# mimic1575.net
KiCad netlist of a schematic drawn in EAGLE
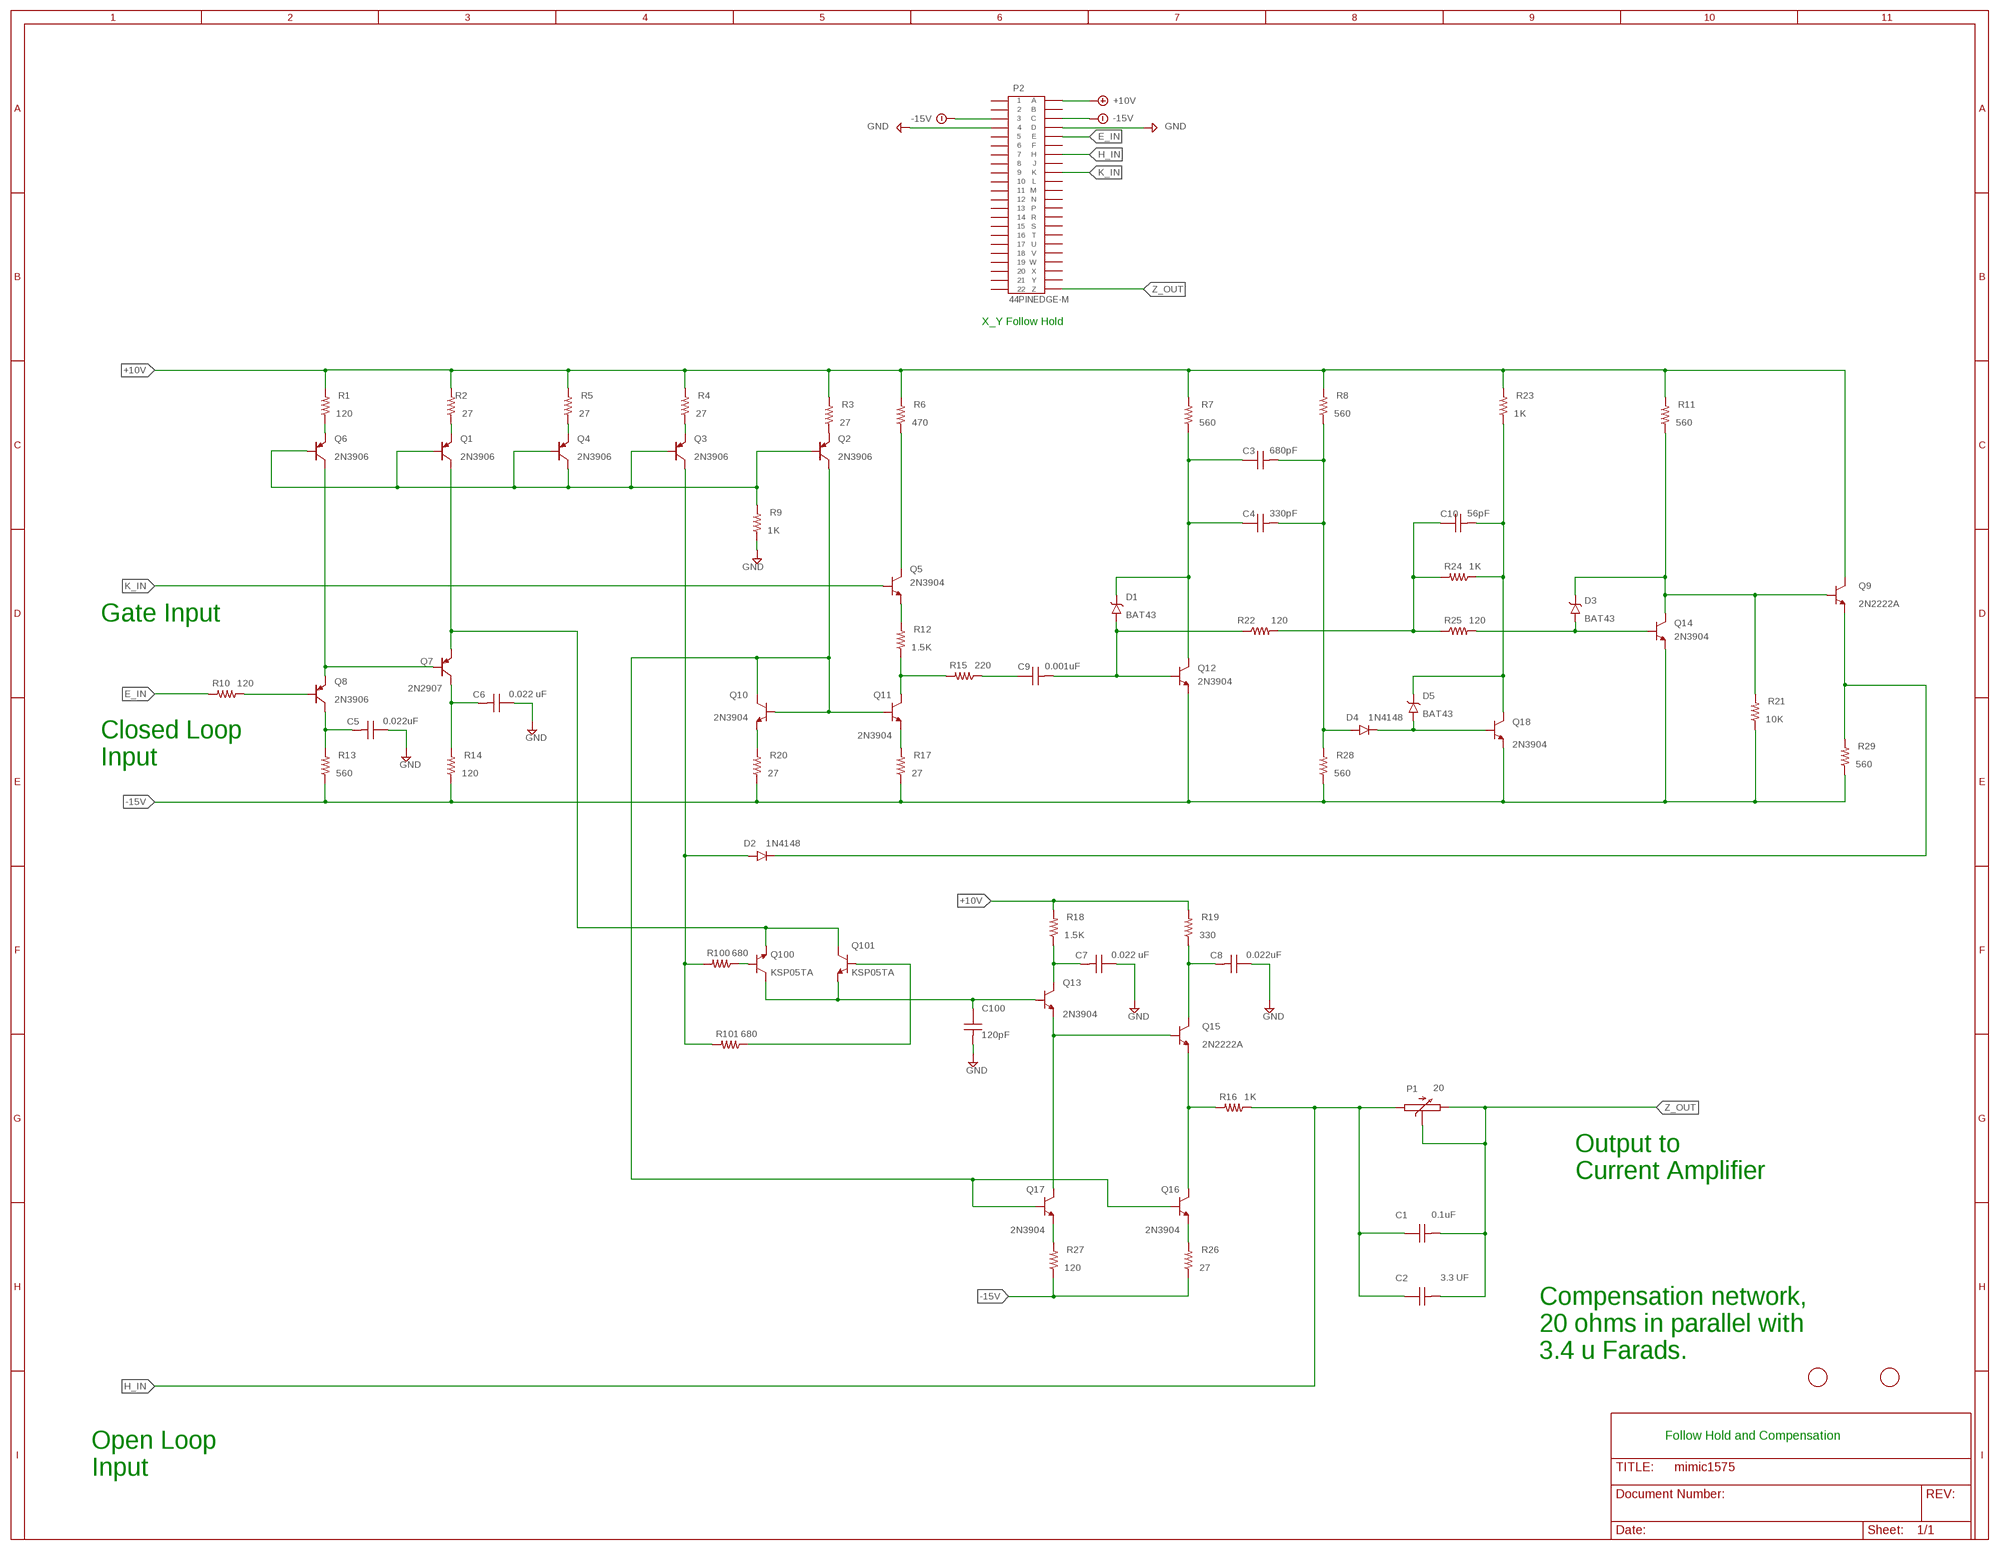
[diagram p0: schematic, sheet 1]

(export (version "E")
  (design (tool "Eeschema 10.0.6"))
  (components
    (comp (ref "C1")
      (value "0.1uF")
      (footprint "eagle-import:5MM_TH")
      (fields (field (name "MPN") "FA26X8R2A104KNU06"))
      (libsource (lib "eagle-import") (part "CAP0.1UF100V"))
    )
    (comp (ref "C2")
      (value "3.3 UF")
      (footprint "eagle-import:ECW-FD2W335K")
      (libsource (lib "eagle-import") (part "ECW-FD2W335K"))
    )
    (comp (ref "C3")
      (value "680pF")
      (footprint "eagle-import:5MM_TH")
      (fields (field (name "MPN") "FA26X8R2A104KNU06") (field (name "MPN_1") "1000 pf"))
      (libsource (lib "eagle-import") (part "CAP0.1UF100V"))
    )
    (comp (ref "C4")
      (value "330pF")
      (footprint "eagle-import:5MM_TH")
      (fields (field (name "MPN") "FA26X8R2A104KNU06") (field (name "MPN_1") "1000 pf"))
      (libsource (lib "eagle-import") (part "CAP0.1UF100V"))
    )
    (comp (ref "C5")
      (value "0.022uF")
      (footprint "eagle-import:CAP-ZERO-PT-ZERO-22UF-250V-FILM")
      (libsource (lib "eagle-import") (part "ECQ-E2223JF"))
    )
    (comp (ref "C6")
      (value "0.022 uF")
      (footprint "eagle-import:CAP-ZERO-PT-ZERO-22UF-250V-FILM")
      (libsource (lib "eagle-import") (part "ECQ-E2223JF"))
    )
    (comp (ref "C7")
      (value "0.022 uF")
      (footprint "eagle-import:CAP-ZERO-PT-ZERO-22UF-250V-FILM")
      (libsource (lib "eagle-import") (part "ECQ-E2223JF"))
    )
    (comp (ref "C8")
      (value "0.022uF")
      (footprint "eagle-import:CAP-ZERO-PT-ZERO-22UF-250V-FILM")
      (libsource (lib "eagle-import") (part "ECQ-E2223JF"))
    )
    (comp (ref "C9")
      (value "0.001uF")
      (footprint "eagle-import:5MM_TH")
      (fields (field (name "MPN") "FA26X8R2A104KNU06") (field (name "MPN_1") "1000 pf"))
      (libsource (lib "eagle-import") (part "CAP0.1UF100V"))
    )
    (comp (ref "C10")
      (value "56pF")
      (footprint "eagle-import:5MM_TH")
      (fields (field (name "MPN") "FA26X8R2A104KNU06") (field (name "MPN_1") "68 pF"))
      (libsource (lib "eagle-import") (part "CAP0.1UF100V"))
    )
    (comp (ref "C100")
      (value "120pF")
      (footprint "eagle-import:5MM_TH")
      (fields (field (name "MPN") "FA26X8R2A104KNU06") (field (name "MPN_1") "1000 pf"))
      (libsource (lib "eagle-import") (part "CAP0.1UF100V"))
    )
    (comp (ref "D1")
      (value "BAT43")
      (footprint "eagle-import:DO35-7")
      (libsource (lib "eagle-import") (part "1N754A"))
    )
    (comp (ref "D2")
      (value "1N4148")
      (footprint "eagle-import:DO35-7")
      (libsource (lib "eagle-import") (part "1N4148"))
    )
    (comp (ref "D3")
      (value "BAT43")
      (footprint "eagle-import:DO35-7")
      (libsource (lib "eagle-import") (part "1N754A"))
    )
    (comp (ref "D4")
      (value "1N4148")
      (footprint "eagle-import:DO35-7")
      (libsource (lib "eagle-import") (part "1N4148"))
    )
    (comp (ref "D5")
      (value "BAT43")
      (footprint "eagle-import:DO35-7")
      (libsource (lib "eagle-import") (part "1N754A"))
    )
    (comp (ref "P1")
      (value "20")
      (footprint "eagle-import:3006P")
      (libsource (lib "eagle-import") (part "POT-3006P"))
    )
    (comp (ref "P2")
      (value "44PINEDGE-M")
      (footprint "eagle-import:44PINEDGE")
      (libsource (lib "eagle-import") (part "44PINEDGE-M"))
    )
    (comp (ref "Q1")
      (value "2N3906")
      (footprint "eagle-import:TO92")
      (libsource (lib "eagle-import") (part "2N3906"))
    )
    (comp (ref "Q2")
      (value "2N3906")
      (footprint "eagle-import:TO92")
      (libsource (lib "eagle-import") (part "2N3906"))
    )
    (comp (ref "Q3")
      (value "2N3906")
      (footprint "eagle-import:TO92")
      (libsource (lib "eagle-import") (part "2N3906"))
    )
    (comp (ref "Q4")
      (value "2N3906")
      (footprint "eagle-import:TO92")
      (libsource (lib "eagle-import") (part "2N3906"))
    )
    (comp (ref "Q5")
      (value "2N3904")
      (footprint "eagle-import:TO92")
      (libsource (lib "eagle-import") (part "2N3904"))
    )
    (comp (ref "Q6")
      (value "2N3906")
      (footprint "eagle-import:TO92")
      (libsource (lib "eagle-import") (part "2N3906"))
    )
    (comp (ref "Q7")
      (value "2N2907")
      (footprint "eagle-import:TO18")
      (libsource (lib "eagle-import") (part "2N2907"))
    )
    (comp (ref "Q8")
      (value "2N3906")
      (footprint "eagle-import:TO92")
      (libsource (lib "eagle-import") (part "2N3906"))
    )
    (comp (ref "Q9")
      (value "2N2222A")
      (footprint "eagle-import:TO18")
      (libsource (lib "eagle-import") (part "2N2222A"))
    )
    (comp (ref "Q10")
      (value "2N3904")
      (footprint "eagle-import:TO92")
      (libsource (lib "eagle-import") (part "2N3904"))
    )
    (comp (ref "Q11")
      (value "2N3904")
      (footprint "eagle-import:TO92")
      (libsource (lib "eagle-import") (part "2N3904"))
    )
    (comp (ref "Q12")
      (value "2N3904")
      (footprint "eagle-import:TO92")
      (libsource (lib "eagle-import") (part "2N3904"))
    )
    (comp (ref "Q13")
      (value "2N3904")
      (footprint "eagle-import:TO92")
      (libsource (lib "eagle-import") (part "2N3904"))
    )
    (comp (ref "Q14")
      (value "2N3904")
      (footprint "eagle-import:TO92")
      (libsource (lib "eagle-import") (part "2N3904"))
    )
    (comp (ref "Q15")
      (value "2N2222A")
      (footprint "eagle-import:TO18")
      (libsource (lib "eagle-import") (part "2N2222A"))
    )
    (comp (ref "Q16")
      (value "2N3904")
      (footprint "eagle-import:TO92")
      (libsource (lib "eagle-import") (part "2N3904"))
    )
    (comp (ref "Q17")
      (value "2N3904")
      (footprint "eagle-import:TO92")
      (libsource (lib "eagle-import") (part "2N3904"))
    )
    (comp (ref "Q18")
      (value "2N3904")
      (footprint "eagle-import:TO92")
      (libsource (lib "eagle-import") (part "2N3904"))
    )
    (comp (ref "Q100")
      (value "KSP05TA")
      (footprint "eagle-import:TO92")
      (libsource (lib "eagle-import") (part "KSP05TA"))
    )
    (comp (ref "Q101")
      (value "KSP05TA")
      (footprint "eagle-import:TO92")
      (libsource (lib "eagle-import") (part "KSP05TA"))
    )
    (comp (ref "R1")
      (value "120")
      (footprint "eagle-import:R_QUARTERWATT")
      (libsource (lib "eagle-import") (part "AXIALRESISTORQUARTER_WATT"))
    )
    (comp (ref "R2")
      (value "27")
      (footprint "eagle-import:R_QUARTERWATT")
      (libsource (lib "eagle-import") (part "AXIALRESISTORQUARTER_WATT"))
    )
    (comp (ref "R3")
      (value "27")
      (footprint "eagle-import:R_QUARTERWATT")
      (libsource (lib "eagle-import") (part "AXIALRESISTORQUARTER_WATT"))
    )
    (comp (ref "R4")
      (value "27")
      (footprint "eagle-import:R_QUARTERWATT")
      (libsource (lib "eagle-import") (part "AXIALRESISTORQUARTER_WATT"))
    )
    (comp (ref "R5")
      (value "27")
      (footprint "eagle-import:R_QUARTERWATT")
      (libsource (lib "eagle-import") (part "AXIALRESISTORQUARTER_WATT"))
    )
    (comp (ref "R6")
      (value "470")
      (footprint "eagle-import:R_QUARTERWATT")
      (libsource (lib "eagle-import") (part "AXIALRESISTORQUARTER_WATT"))
    )
    (comp (ref "R7")
      (value "560")
      (footprint "eagle-import:R_QUARTERWATT")
      (libsource (lib "eagle-import") (part "AXIALRESISTORQUARTER_WATT"))
    )
    (comp (ref "R8")
      (value "560")
      (footprint "eagle-import:R_QUARTERWATT")
      (libsource (lib "eagle-import") (part "AXIALRESISTORQUARTER_WATT"))
    )
    (comp (ref "R9")
      (value "1K")
      (footprint "eagle-import:R_QUARTERWATT")
      (libsource (lib "eagle-import") (part "AXIALRESISTORQUARTER_WATT"))
    )
    (comp (ref "R10")
      (value "120")
      (footprint "eagle-import:R_QUARTERWATT")
      (libsource (lib "eagle-import") (part "AXIALRESISTORQUARTER_WATT"))
    )
    (comp (ref "R11")
      (value "560")
      (footprint "eagle-import:R_QUARTERWATT")
      (libsource (lib "eagle-import") (part "AXIALRESISTORQUARTER_WATT"))
    )
    (comp (ref "R12")
      (value "1.5K")
      (footprint "eagle-import:R_QUARTERWATT")
      (libsource (lib "eagle-import") (part "AXIALRESISTORQUARTER_WATT"))
    )
    (comp (ref "R13")
      (value "560")
      (footprint "eagle-import:R_QUARTERWATT")
      (libsource (lib "eagle-import") (part "AXIALRESISTORQUARTER_WATT"))
    )
    (comp (ref "R14")
      (value "120")
      (footprint "eagle-import:R_QUARTERWATT")
      (libsource (lib "eagle-import") (part "AXIALRESISTORQUARTER_WATT"))
    )
    (comp (ref "R15")
      (value "220")
      (footprint "eagle-import:R_QUARTERWATT")
      (libsource (lib "eagle-import") (part "AXIALRESISTORQUARTER_WATT"))
    )
    (comp (ref "R16")
      (value "1K")
      (footprint "eagle-import:R_QUARTERWATT")
      (libsource (lib "eagle-import") (part "AXIALRESISTORQUARTER_WATT"))
    )
    (comp (ref "R17")
      (value "27")
      (footprint "eagle-import:R_QUARTERWATT")
      (libsource (lib "eagle-import") (part "AXIALRESISTORQUARTER_WATT"))
    )
    (comp (ref "R18")
      (value "1.5K")
      (footprint "eagle-import:R_QUARTERWATT")
      (libsource (lib "eagle-import") (part "AXIALRESISTORQUARTER_WATT"))
    )
    (comp (ref "R19")
      (value "330")
      (footprint "eagle-import:R_QUARTERWATT")
      (libsource (lib "eagle-import") (part "AXIALRESISTORQUARTER_WATT"))
    )
    (comp (ref "R20")
      (value "27")
      (footprint "eagle-import:R_QUARTERWATT")
      (libsource (lib "eagle-import") (part "AXIALRESISTORQUARTER_WATT"))
    )
    (comp (ref "R21")
      (value "10K")
      (footprint "eagle-import:R_QUARTERWATT")
      (libsource (lib "eagle-import") (part "AXIALRESISTORQUARTER_WATT"))
    )
    (comp (ref "R22")
      (value "120")
      (footprint "eagle-import:R_QUARTERWATT")
      (libsource (lib "eagle-import") (part "AXIALRESISTORQUARTER_WATT"))
    )
    (comp (ref "R23")
      (value "1K")
      (footprint "eagle-import:R_QUARTERWATT")
      (libsource (lib "eagle-import") (part "AXIALRESISTORQUARTER_WATT"))
    )
    (comp (ref "R24")
      (value "1K")
      (footprint "eagle-import:R_QUARTERWATT")
      (libsource (lib "eagle-import") (part "AXIALRESISTORQUARTER_WATT"))
    )
    (comp (ref "R25")
      (value "120")
      (footprint "eagle-import:R_QUARTERWATT")
      (libsource (lib "eagle-import") (part "AXIALRESISTORQUARTER_WATT"))
    )
    (comp (ref "R26")
      (value "27")
      (footprint "eagle-import:R_QUARTERWATT")
      (libsource (lib "eagle-import") (part "AXIALRESISTORQUARTER_WATT"))
    )
    (comp (ref "R27")
      (value "120")
      (footprint "eagle-import:R_QUARTERWATT")
      (libsource (lib "eagle-import") (part "AXIALRESISTORQUARTER_WATT"))
    )
    (comp (ref "R28")
      (value "560")
      (footprint "eagle-import:R_QUARTERWATT")
      (libsource (lib "eagle-import") (part "AXIALRESISTORQUARTER_WATT"))
    )
    (comp (ref "R29")
      (value "560")
      (footprint "eagle-import:R_QUARTERWATT")
      (libsource (lib "eagle-import") (part "AXIALRESISTORQUARTER_WATT"))
    )
    (comp (ref "R100")
      (value "680")
      (footprint "eagle-import:R_QUARTERWATT")
      (libsource (lib "eagle-import") (part "AXIALRESISTORQUARTER_WATT"))
    )
    (comp (ref "R101")
      (value "680")
      (footprint "eagle-import:R_QUARTERWATT")
      (libsource (lib "eagle-import") (part "AXIALRESISTORQUARTER_WATT"))
    )
    (comp (ref "U$1")
      (value "FIDUCIAL")
      (footprint "eagle-import:FIDUCIAL_1MM")
      (libsource (lib "eagle-import") (part "FIDUCIAL"))
    )
    (comp (ref "U$2")
      (value "FIDUCIAL")
      (footprint "eagle-import:FIDUCIAL_1MM")
      (libsource (lib "eagle-import") (part "FIDUCIAL"))
    )
  )
  (nets
    (net (code "1") (name "+10V") (class "Default")
      (node (ref "P2") (pin "A") (pinfunction "A_A") (pintype "passive"))
      (node (ref "Q9") (pin "3") (pinfunction "C_3") (pintype "passive"))
      (node (ref "R1") (pin "2") (pinfunction "P$2_2") (pintype "passive"))
      (node (ref "R11") (pin "2") (pinfunction "P$2_2") (pintype "passive"))
      (node (ref "R18") (pin "2") (pinfunction "P$2_2") (pintype "passive"))
      (node (ref "R19") (pin "2") (pinfunction "P$2_2") (pintype "passive"))
      (node (ref "R2") (pin "2") (pinfunction "P$2_2") (pintype "passive"))
      (node (ref "R23") (pin "2") (pinfunction "P$2_2") (pintype "passive"))
      (node (ref "R3") (pin "2") (pinfunction "P$2_2") (pintype "passive"))
      (node (ref "R4") (pin "2") (pinfunction "P$2_2") (pintype "passive"))
      (node (ref "R5") (pin "2") (pinfunction "P$2_2") (pintype "passive"))
      (node (ref "R6") (pin "2") (pinfunction "P$2_2") (pintype "passive"))
      (node (ref "R7") (pin "2") (pinfunction "P$2_2") (pintype "passive"))
      (node (ref "R8") (pin "2") (pinfunction "P$2_2") (pintype "passive"))
    )
    (net (code "2") (name "-15V") (class "Default")
      (node (ref "P2") (pin "3") (pinfunction "3_3") (pintype "passive"))
      (node (ref "P2") (pin "C") (pinfunction "C_C") (pintype "passive"))
      (node (ref "Q12") (pin "1") (pinfunction "E_1") (pintype "passive"))
      (node (ref "Q14") (pin "1") (pinfunction "E_1") (pintype "passive"))
      (node (ref "Q18") (pin "1") (pinfunction "E_1") (pintype "passive"))
      (node (ref "R13") (pin "1") (pinfunction "P$1_1") (pintype "passive"))
      (node (ref "R14") (pin "1") (pinfunction "P$1_1") (pintype "passive"))
      (node (ref "R17") (pin "1") (pinfunction "P$1_1") (pintype "passive"))
      (node (ref "R20") (pin "1") (pinfunction "P$1_1") (pintype "passive"))
      (node (ref "R21") (pin "1") (pinfunction "P$1_1") (pintype "passive"))
      (node (ref "R26") (pin "1") (pinfunction "P$1_1") (pintype "passive"))
      (node (ref "R27") (pin "1") (pinfunction "P$1_1") (pintype "passive"))
      (node (ref "R28") (pin "1") (pinfunction "P$1_1") (pintype "passive"))
      (node (ref "R29") (pin "1") (pinfunction "P$1_1") (pintype "passive"))
    )
    (net (code "3") (name "E_IN") (class "Default")
      (node (ref "P2") (pin "E") (pinfunction "E_E") (pintype "passive"))
      (node (ref "R10") (pin "2") (pinfunction "P$2_2") (pintype "passive"))
    )
    (net (code "4") (name "GND") (class "Default")
      (node (ref "C100") (pin "2") (pinfunction "2_2") (pintype "passive"))
      (node (ref "C5") (pin "1") (pinfunction "1_1") (pintype "passive"))
      (node (ref "C6") (pin "1") (pinfunction "1_1") (pintype "passive"))
      (node (ref "C7") (pin "1") (pinfunction "1_1") (pintype "passive"))
      (node (ref "C8") (pin "1") (pinfunction "1_1") (pintype "passive"))
      (node (ref "P2") (pin "4") (pinfunction "4_4") (pintype "passive"))
      (node (ref "P2") (pin "D") (pinfunction "D_D") (pintype "passive"))
      (node (ref "R9") (pin "1") (pinfunction "P$1_1") (pintype "passive"))
    )
    (net (code "5") (name "H_IN") (class "Default")
      (node (ref "C1") (pin "1") (pinfunction "1_1") (pintype "passive"))
      (node (ref "C2") (pin "1") (pinfunction "1_1") (pintype "passive"))
      (node (ref "P1") (pin "1") (pinfunction "1_1") (pintype "passive"))
      (node (ref "P2") (pin "H") (pinfunction "H_H") (pintype "passive"))
      (node (ref "R16") (pin "1") (pinfunction "P$1_1") (pintype "passive"))
    )
    (net (code "6") (name "K_IN") (class "Default")
      (node (ref "P2") (pin "K") (pinfunction "K_K") (pintype "passive"))
      (node (ref "Q5") (pin "2") (pinfunction "B_2") (pintype "passive"))
    )
    (net (code "7") (name "Net-(Q1-B)") (class "Default")
      (node (ref "Q1") (pin "2") (pinfunction "B_2") (pintype "passive"))
      (node (ref "Q2") (pin "2") (pinfunction "B_2") (pintype "passive"))
      (node (ref "Q3") (pin "2") (pinfunction "B_2") (pintype "passive"))
      (node (ref "Q4") (pin "1") (pinfunction "C_1") (pintype "passive"))
      (node (ref "Q4") (pin "2") (pinfunction "B_2") (pintype "passive"))
      (node (ref "Q6") (pin "2") (pinfunction "B_2") (pintype "passive"))
      (node (ref "R9") (pin "2") (pinfunction "P$2_2") (pintype "passive"))
    )
    (net (code "8") (name "Net-(Q1-C)") (class "Default")
      (node (ref "Q1") (pin "1") (pinfunction "C_1") (pintype "passive"))
      (node (ref "Q100") (pin "1") (pinfunction "E_1") (pintype "passive"))
      (node (ref "Q101") (pin "3") (pinfunction "C_3") (pintype "passive"))
      (node (ref "Q7") (pin "1") (pinfunction "E_1") (pintype "passive"))
    )
    (net (code "9") (name "Net-(Q1-E)") (class "Default")
      (node (ref "Q1") (pin "3") (pinfunction "E_3") (pintype "passive"))
      (node (ref "R2") (pin "1") (pinfunction "P$1_1") (pintype "passive"))
    )
    (net (code "10") (name "Net-(Q2-E)") (class "Default")
      (node (ref "Q2") (pin "3") (pinfunction "E_3") (pintype "passive"))
      (node (ref "R3") (pin "1") (pinfunction "P$1_1") (pintype "passive"))
    )
    (net (code "11") (name "Net-(Q3-C)") (class "Default")
      (node (ref "D2") (pin "A") (pinfunction "A_A") (pintype "passive"))
      (node (ref "Q3") (pin "1") (pinfunction "C_1") (pintype "passive"))
      (node (ref "R100") (pin "2") (pinfunction "P$2_2") (pintype "passive"))
      (node (ref "R101") (pin "2") (pinfunction "P$2_2") (pintype "passive"))
    )
    (net (code "12") (name "Net-(Q3-E)") (class "Default")
      (node (ref "Q3") (pin "3") (pinfunction "E_3") (pintype "passive"))
      (node (ref "R4") (pin "1") (pinfunction "P$1_1") (pintype "passive"))
    )
    (net (code "13") (name "Net-(Q4-E)") (class "Default")
      (node (ref "Q4") (pin "3") (pinfunction "E_3") (pintype "passive"))
      (node (ref "R5") (pin "1") (pinfunction "P$1_1") (pintype "passive"))
    )
    (net (code "14") (name "Net-(Q5-C)") (class "Default")
      (node (ref "Q5") (pin "3") (pinfunction "C_3") (pintype "passive"))
      (node (ref "R6") (pin "1") (pinfunction "P$1_1") (pintype "passive"))
    )
    (net (code "15") (name "Net-(Q5-E)") (class "Default")
      (node (ref "Q5") (pin "1") (pinfunction "E_1") (pintype "passive"))
      (node (ref "R12") (pin "2") (pinfunction "P$2_2") (pintype "passive"))
    )
    (net (code "16") (name "Net-(Q6-C)") (class "Default")
      (node (ref "Q6") (pin "1") (pinfunction "C_1") (pintype "passive"))
      (node (ref "Q7") (pin "2") (pinfunction "B_2") (pintype "passive"))
      (node (ref "Q8") (pin "3") (pinfunction "E_3") (pintype "passive"))
    )
    (net (code "17") (name "Net-(Q6-E)") (class "Default")
      (node (ref "Q6") (pin "3") (pinfunction "E_3") (pintype "passive"))
      (node (ref "R1") (pin "1") (pinfunction "P$1_1") (pintype "passive"))
    )
    (net (code "18") (name "Net-(Q7-C)") (class "Default")
      (node (ref "C6") (pin "2") (pinfunction "2_2") (pintype "passive"))
      (node (ref "Q7") (pin "3") (pinfunction "C_3") (pintype "passive"))
      (node (ref "R14") (pin "2") (pinfunction "P$2_2") (pintype "passive"))
    )
    (net (code "19") (name "Net-(Q8-B)") (class "Default")
      (node (ref "Q8") (pin "2") (pinfunction "B_2") (pintype "passive"))
      (node (ref "R10") (pin "1") (pinfunction "P$1_1") (pintype "passive"))
    )
    (net (code "20") (name "Net-(Q8-C)") (class "Default")
      (node (ref "C5") (pin "2") (pinfunction "2_2") (pintype "passive"))
      (node (ref "Q8") (pin "1") (pinfunction "C_1") (pintype "passive"))
      (node (ref "R13") (pin "2") (pinfunction "P$2_2") (pintype "passive"))
    )
    (net (code "21") (name "Net-(Q9-E)") (class "Default")
      (node (ref "D2") (pin "C") (pinfunction "C_C") (pintype "passive"))
      (node (ref "Q9") (pin "1") (pinfunction "E_1") (pintype "passive"))
      (node (ref "R29") (pin "2") (pinfunction "P$2_2") (pintype "passive"))
    )
    (net (code "22") (name "Net-(Q10-B)") (class "Default")
      (node (ref "Q10") (pin "2") (pinfunction "B_2") (pintype "passive"))
      (node (ref "Q10") (pin "3") (pinfunction "C_3") (pintype "passive"))
      (node (ref "Q11") (pin "2") (pinfunction "B_2") (pintype "passive"))
      (node (ref "Q16") (pin "2") (pinfunction "B_2") (pintype "passive"))
      (node (ref "Q17") (pin "2") (pinfunction "B_2") (pintype "passive"))
      (node (ref "Q2") (pin "1") (pinfunction "C_1") (pintype "passive"))
    )
    (net (code "23") (name "Net-(Q10-E)") (class "Default")
      (node (ref "Q10") (pin "1") (pinfunction "E_1") (pintype "passive"))
      (node (ref "R20") (pin "2") (pinfunction "P$2_2") (pintype "passive"))
    )
    (net (code "24") (name "Net-(Q11-C)") (class "Default")
      (node (ref "Q11") (pin "3") (pinfunction "C_3") (pintype "passive"))
      (node (ref "R12") (pin "1") (pinfunction "P$1_1") (pintype "passive"))
      (node (ref "R15") (pin "2") (pinfunction "P$2_2") (pintype "passive"))
    )
    (net (code "25") (name "Net-(Q11-E)") (class "Default")
      (node (ref "Q11") (pin "1") (pinfunction "E_1") (pintype "passive"))
      (node (ref "R17") (pin "2") (pinfunction "P$2_2") (pintype "passive"))
    )
    (net (code "26") (name "Net-(Q12-B)") (class "Default")
      (node (ref "C9") (pin "2") (pinfunction "2_2") (pintype "passive"))
      (node (ref "D1") (pin "A") (pinfunction "A_A") (pintype "passive"))
      (node (ref "Q12") (pin "2") (pinfunction "B_2") (pintype "passive"))
      (node (ref "R22") (pin "1") (pinfunction "P$1_1") (pintype "passive"))
    )
    (net (code "27") (name "Net-(Q12-C)") (class "Default")
      (node (ref "C3") (pin "1") (pinfunction "1_1") (pintype "passive"))
      (node (ref "C4") (pin "1") (pinfunction "1_1") (pintype "passive"))
      (node (ref "D1") (pin "C") (pinfunction "C_C") (pintype "passive"))
      (node (ref "Q12") (pin "3") (pinfunction "C_3") (pintype "passive"))
      (node (ref "R7") (pin "1") (pinfunction "P$1_1") (pintype "passive"))
    )
    (net (code "28") (name "Net-(Q13-C)") (class "Default")
      (node (ref "C7") (pin "2") (pinfunction "2_2") (pintype "passive"))
      (node (ref "Q13") (pin "3") (pinfunction "C_3") (pintype "passive"))
      (node (ref "R18") (pin "1") (pinfunction "P$1_1") (pintype "passive"))
    )
    (net (code "29") (name "Net-(Q13-E)") (class "Default")
      (node (ref "Q13") (pin "1") (pinfunction "E_1") (pintype "passive"))
      (node (ref "Q15") (pin "2") (pinfunction "B_2") (pintype "passive"))
      (node (ref "Q17") (pin "3") (pinfunction "C_3") (pintype "passive"))
    )
    (net (code "30") (name "Net-(Q14-B)") (class "Default")
      (node (ref "D3") (pin "A") (pinfunction "A_A") (pintype "passive"))
      (node (ref "Q14") (pin "2") (pinfunction "B_2") (pintype "passive"))
      (node (ref "R25") (pin "2") (pinfunction "P$2_2") (pintype "passive"))
    )
    (net (code "31") (name "Net-(Q14-C)") (class "Default")
      (node (ref "D3") (pin "C") (pinfunction "C_C") (pintype "passive"))
      (node (ref "Q14") (pin "3") (pinfunction "C_3") (pintype "passive"))
      (node (ref "Q9") (pin "2") (pinfunction "B_2") (pintype "passive"))
      (node (ref "R11") (pin "1") (pinfunction "P$1_1") (pintype "passive"))
      (node (ref "R21") (pin "2") (pinfunction "P$2_2") (pintype "passive"))
    )
    (net (code "32") (name "Net-(Q15-C)") (class "Default")
      (node (ref "C8") (pin "2") (pinfunction "2_2") (pintype "passive"))
      (node (ref "Q15") (pin "3") (pinfunction "C_3") (pintype "passive"))
      (node (ref "R19") (pin "1") (pinfunction "P$1_1") (pintype "passive"))
    )
    (net (code "33") (name "Net-(Q15-E)") (class "Default")
      (node (ref "Q15") (pin "1") (pinfunction "E_1") (pintype "passive"))
      (node (ref "Q16") (pin "3") (pinfunction "C_3") (pintype "passive"))
      (node (ref "R16") (pin "2") (pinfunction "P$2_2") (pintype "passive"))
    )
    (net (code "34") (name "Net-(Q16-E)") (class "Default")
      (node (ref "Q16") (pin "1") (pinfunction "E_1") (pintype "passive"))
      (node (ref "R26") (pin "2") (pinfunction "P$2_2") (pintype "passive"))
    )
    (net (code "35") (name "Net-(Q17-E)") (class "Default")
      (node (ref "Q17") (pin "1") (pinfunction "E_1") (pintype "passive"))
      (node (ref "R27") (pin "2") (pinfunction "P$2_2") (pintype "passive"))
    )
    (net (code "36") (name "Net-(Q18-B)") (class "Default")
      (node (ref "D4") (pin "C") (pinfunction "C_C") (pintype "passive"))
      (node (ref "D5") (pin "A") (pinfunction "A_A") (pintype "passive"))
      (node (ref "Q18") (pin "2") (pinfunction "B_2") (pintype "passive"))
    )
    (net (code "37") (name "Net-(Q18-C)") (class "Default")
      (node (ref "C10") (pin "2") (pinfunction "2_2") (pintype "passive"))
      (node (ref "D5") (pin "C") (pinfunction "C_C") (pintype "passive"))
      (node (ref "Q18") (pin "3") (pinfunction "C_3") (pintype "passive"))
      (node (ref "R23") (pin "1") (pinfunction "P$1_1") (pintype "passive"))
      (node (ref "R24") (pin "1") (pinfunction "P$1_1") (pintype "passive"))
    )
    (net (code "38") (name "Net-(Q100-B)") (class "Default")
      (node (ref "Q100") (pin "2") (pinfunction "B_2") (pintype "passive"))
      (node (ref "R100") (pin "1") (pinfunction "P$1_1") (pintype "passive"))
    )
    (net (code "39") (name "Net-(Q100-C)") (class "Default")
      (node (ref "C100") (pin "1") (pinfunction "1_1") (pintype "passive"))
      (node (ref "Q100") (pin "3") (pinfunction "C_3") (pintype "passive"))
      (node (ref "Q101") (pin "1") (pinfunction "E_1") (pintype "passive"))
      (node (ref "Q13") (pin "2") (pinfunction "B_2") (pintype "passive"))
    )
    (net (code "40") (name "Net-(Q101-B)") (class "Default")
      (node (ref "Q101") (pin "2") (pinfunction "B_2") (pintype "passive"))
      (node (ref "R101") (pin "1") (pinfunction "P$1_1") (pintype "passive"))
    )
    (net (code "41") (name "Net-(R15-P$1)") (class "Default")
      (node (ref "C9") (pin "1") (pinfunction "1_1") (pintype "passive"))
      (node (ref "R15") (pin "1") (pinfunction "P$1_1") (pintype "passive"))
    )
    (net (code "42") (name "Net-(R22-P$2)") (class "Default")
      (node (ref "C10") (pin "1") (pinfunction "1_1") (pintype "passive"))
      (node (ref "R22") (pin "2") (pinfunction "P$2_2") (pintype "passive"))
      (node (ref "R24") (pin "2") (pinfunction "P$2_2") (pintype "passive"))
      (node (ref "R25") (pin "1") (pinfunction "P$1_1") (pintype "passive"))
    )
    (net (code "43") (name "Net-(R28-P$2)") (class "Default")
      (node (ref "C3") (pin "2") (pinfunction "2_2") (pintype "passive"))
      (node (ref "C4") (pin "2") (pinfunction "2_2") (pintype "passive"))
      (node (ref "D4") (pin "A") (pinfunction "A_A") (pintype "passive"))
      (node (ref "R28") (pin "2") (pinfunction "P$2_2") (pintype "passive"))
      (node (ref "R8") (pin "1") (pinfunction "P$1_1") (pintype "passive"))
    )
    (net (code "44") (name "Z_OUT") (class "Default")
      (node (ref "C1") (pin "2") (pinfunction "2_2") (pintype "passive"))
      (node (ref "C2") (pin "2") (pinfunction "2_2") (pintype "passive"))
      (node (ref "P1") (pin "2") (pinfunction "2_2") (pintype "passive"))
      (node (ref "P1") (pin "3") (pinfunction "3_3") (pintype "passive"))
      (node (ref "P2") (pin "Z") (pinfunction "Z_Z") (pintype "passive"))
    )
    (net (code "45") (name "unconnected-(P2-Pad1)") (class "Default")
      (node (ref "P2") (pin "1") (pinfunction "1_1") (pintype "passive"))
    )
    (net (code "46") (name "unconnected-(P2-Pad2)") (class "Default")
      (node (ref "P2") (pin "2") (pinfunction "2_2") (pintype "passive"))
    )
    (net (code "47") (name "unconnected-(P2-Pad5)") (class "Default")
      (node (ref "P2") (pin "5") (pinfunction "5_5") (pintype "passive"))
    )
    (net (code "48") (name "unconnected-(P2-Pad6)") (class "Default")
      (node (ref "P2") (pin "6") (pinfunction "6_6") (pintype "passive"))
    )
    (net (code "49") (name "unconnected-(P2-Pad7)") (class "Default")
      (node (ref "P2") (pin "7") (pinfunction "7_7") (pintype "passive"))
    )
    (net (code "50") (name "unconnected-(P2-Pad8)") (class "Default")
      (node (ref "P2") (pin "8") (pinfunction "8_8") (pintype "passive"))
    )
    (net (code "51") (name "unconnected-(P2-Pad9)") (class "Default")
      (node (ref "P2") (pin "9") (pinfunction "9_9") (pintype "passive"))
    )
    (net (code "52") (name "unconnected-(P2-Pad10)") (class "Default")
      (node (ref "P2") (pin "10") (pinfunction "10_10") (pintype "passive"))
    )
    (net (code "53") (name "unconnected-(P2-Pad11)") (class "Default")
      (node (ref "P2") (pin "11") (pinfunction "11_11") (pintype "passive"))
    )
    (net (code "54") (name "unconnected-(P2-Pad12)") (class "Default")
      (node (ref "P2") (pin "12") (pinfunction "12_12") (pintype "passive"))
    )
    (net (code "55") (name "unconnected-(P2-Pad13)") (class "Default")
      (node (ref "P2") (pin "13") (pinfunction "13_13") (pintype "passive"))
    )
    (net (code "56") (name "unconnected-(P2-Pad14)") (class "Default")
      (node (ref "P2") (pin "14") (pinfunction "14_14") (pintype "passive"))
    )
    (net (code "57") (name "unconnected-(P2-Pad15)") (class "Default")
      (node (ref "P2") (pin "15") (pinfunction "15_15") (pintype "passive"))
    )
    (net (code "58") (name "unconnected-(P2-Pad16)") (class "Default")
      (node (ref "P2") (pin "16") (pinfunction "16_16") (pintype "passive"))
    )
    (net (code "59") (name "unconnected-(P2-Pad17)") (class "Default")
      (node (ref "P2") (pin "17") (pinfunction "17_17") (pintype "passive"))
    )
    (net (code "60") (name "unconnected-(P2-Pad18)") (class "Default")
      (node (ref "P2") (pin "18") (pinfunction "18_18") (pintype "passive"))
    )
    (net (code "61") (name "unconnected-(P2-Pad19)") (class "Default")
      (node (ref "P2") (pin "19") (pinfunction "19_19") (pintype "passive"))
    )
    (net (code "62") (name "unconnected-(P2-Pad20)") (class "Default")
      (node (ref "P2") (pin "20") (pinfunction "20_20") (pintype "passive"))
    )
    (net (code "63") (name "unconnected-(P2-Pad21)") (class "Default")
      (node (ref "P2") (pin "21") (pinfunction "21_21") (pintype "passive"))
    )
    (net (code "64") (name "unconnected-(P2-Pad22)") (class "Default")
      (node (ref "P2") (pin "22") (pinfunction "22_22") (pintype "passive"))
    )
    (net (code "65") (name "unconnected-(P2-PadB)") (class "Default")
      (node (ref "P2") (pin "B") (pinfunction "B_B") (pintype "passive"))
    )
    (net (code "66") (name "unconnected-(P2-PadF)") (class "Default")
      (node (ref "P2") (pin "F") (pinfunction "F_F") (pintype "passive"))
    )
    (net (code "67") (name "unconnected-(P2-PadJ)") (class "Default")
      (node (ref "P2") (pin "J") (pinfunction "J_J") (pintype "passive"))
    )
    (net (code "68") (name "unconnected-(P2-PadL)") (class "Default")
      (node (ref "P2") (pin "L") (pinfunction "L_L") (pintype "passive"))
    )
    (net (code "69") (name "unconnected-(P2-PadM)") (class "Default")
      (node (ref "P2") (pin "M") (pinfunction "M_M") (pintype "passive"))
    )
    (net (code "70") (name "unconnected-(P2-PadN)") (class "Default")
      (node (ref "P2") (pin "N") (pinfunction "N_N") (pintype "passive"))
    )
    (net (code "71") (name "unconnected-(P2-PadP)") (class "Default")
      (node (ref "P2") (pin "P") (pinfunction "P_P") (pintype "passive"))
    )
    (net (code "72") (name "unconnected-(P2-PadR)") (class "Default")
      (node (ref "P2") (pin "R") (pinfunction "R_R") (pintype "passive"))
    )
    (net (code "73") (name "unconnected-(P2-PadS)") (class "Default")
      (node (ref "P2") (pin "S") (pinfunction "S_S") (pintype "passive"))
    )
    (net (code "74") (name "unconnected-(P2-PadT)") (class "Default")
      (node (ref "P2") (pin "T") (pinfunction "T_T") (pintype "passive"))
    )
    (net (code "75") (name "unconnected-(P2-PadU)") (class "Default")
      (node (ref "P2") (pin "U") (pinfunction "U_U") (pintype "passive"))
    )
    (net (code "76") (name "unconnected-(P2-PadV)") (class "Default")
      (node (ref "P2") (pin "V") (pinfunction "V_V") (pintype "passive"))
    )
    (net (code "77") (name "unconnected-(P2-PadW)") (class "Default")
      (node (ref "P2") (pin "W") (pinfunction "W_W") (pintype "passive"))
    )
    (net (code "78") (name "unconnected-(P2-PadX)") (class "Default")
      (node (ref "P2") (pin "X") (pinfunction "X_X") (pintype "passive"))
    )
    (net (code "79") (name "unconnected-(P2-PadY)") (class "Default")
      (node (ref "P2") (pin "Y") (pinfunction "Y_Y") (pintype "passive"))
    )
  )
)
